# MegaAndLed.net
KiCad netlist of a schematic drawn in EAGLE
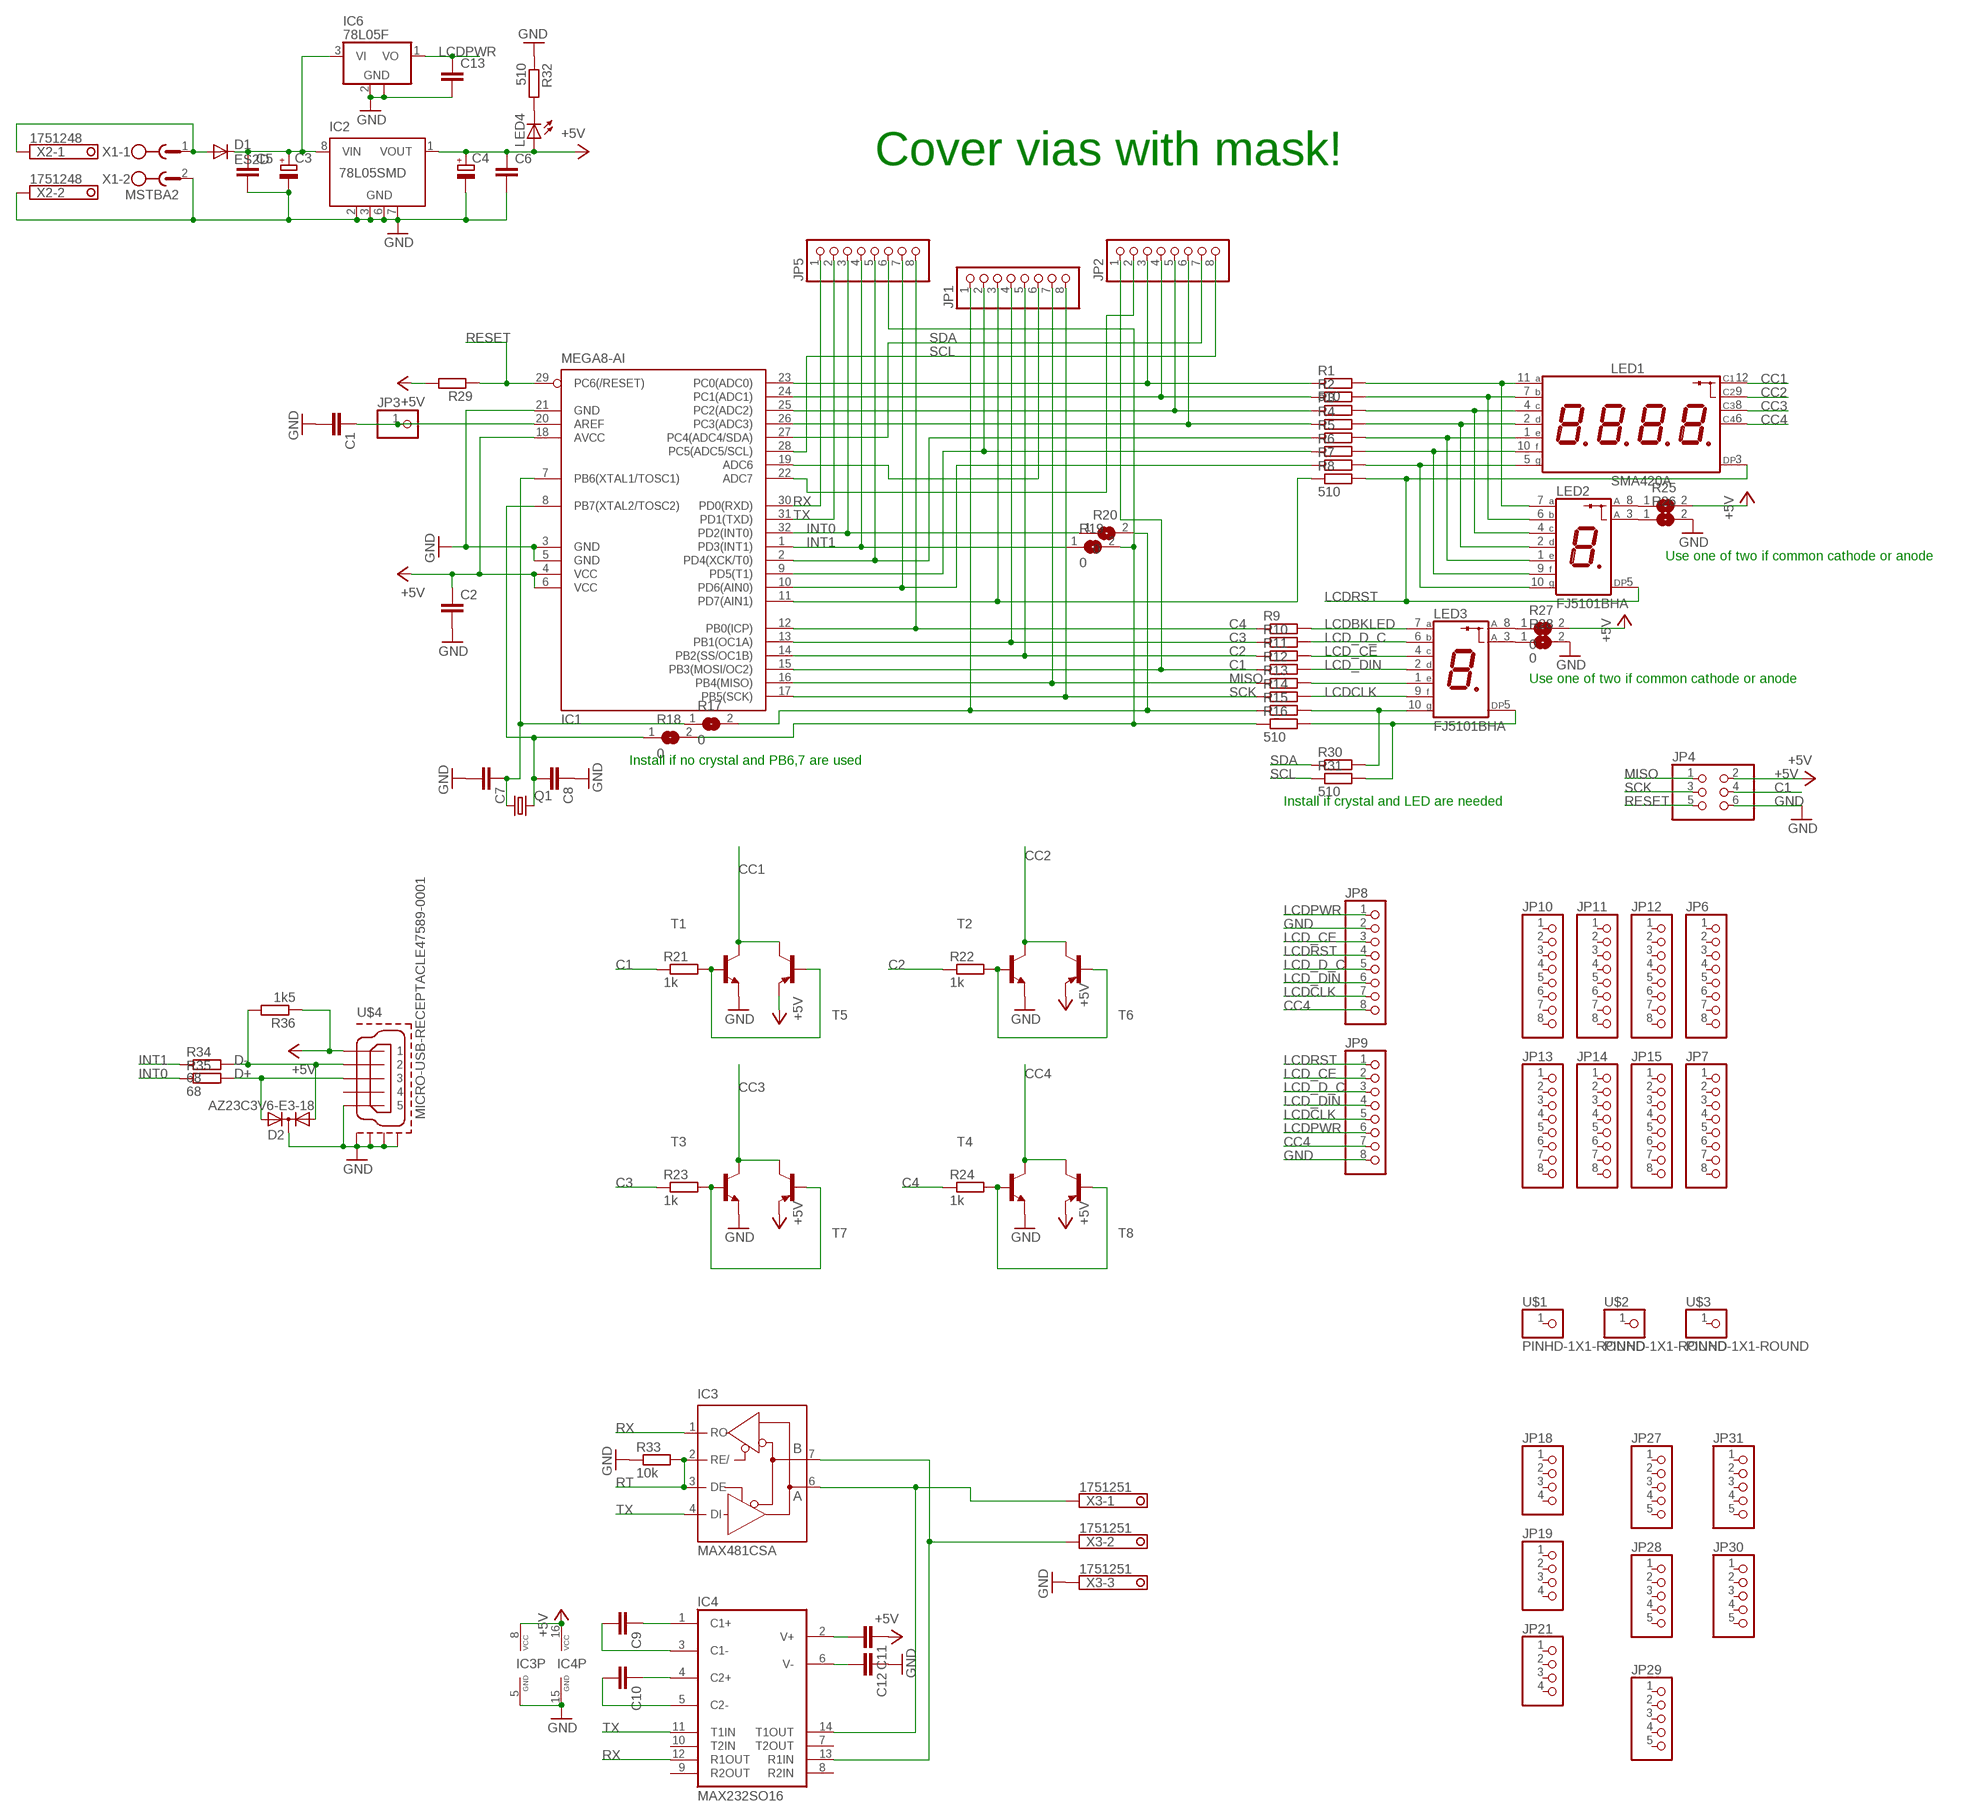
[diagram p0: schematic, sheet 1]

(export (version "E")
  (design (tool "Eeschema 10.0.6"))
  (components
    (comp (ref "C1")
      (value "C-EUC0805")
      (footprint "eagle-import:C0805")
      (libsource (lib "eagle-import") (part "C-EUC0805"))
    )
    (comp (ref "C2")
      (value "C-EUC0805")
      (footprint "eagle-import:C0805")
      (libsource (lib "eagle-import") (part "C-EUC0805"))
    )
    (comp (ref "C3")
      (value "CPOL-EUSMCC")
      (footprint "eagle-import:SMC_C")
      (libsource (lib "eagle-import") (part "CPOL-EUSMCC"))
    )
    (comp (ref "C4")
      (value "CPOL-EUSMCC")
      (footprint "eagle-import:SMC_C")
      (libsource (lib "eagle-import") (part "CPOL-EUSMCC"))
    )
    (comp (ref "C5")
      (value "C-EUC0805")
      (footprint "eagle-import:C0805")
      (libsource (lib "eagle-import") (part "C-EUC0805"))
    )
    (comp (ref "C6")
      (value "C-EUC0805")
      (footprint "eagle-import:C0805")
      (libsource (lib "eagle-import") (part "C-EUC0805"))
    )
    (comp (ref "C7")
      (value "C-EUC0805")
      (footprint "eagle-import:C0805")
      (libsource (lib "eagle-import") (part "C-EUC0805"))
    )
    (comp (ref "C8")
      (value "C-EUC0805")
      (footprint "eagle-import:C0805")
      (libsource (lib "eagle-import") (part "C-EUC0805"))
    )
    (comp (ref "C9")
      (value "C-EUC0805")
      (footprint "eagle-import:C0805")
      (libsource (lib "eagle-import") (part "C-EUC0805"))
    )
    (comp (ref "C10")
      (value "C-EUC0805")
      (footprint "eagle-import:C0805")
      (libsource (lib "eagle-import") (part "C-EUC0805"))
    )
    (comp (ref "C11")
      (value "C-EUC0805")
      (footprint "eagle-import:C0805")
      (libsource (lib "eagle-import") (part "C-EUC0805"))
    )
    (comp (ref "C12")
      (value "C-EUC0805")
      (footprint "eagle-import:C0805")
      (libsource (lib "eagle-import") (part "C-EUC0805"))
    )
    (comp (ref "C13")
      (value "C-EUC0805")
      (footprint "eagle-import:C0805")
      (libsource (lib "eagle-import") (part "C-EUC0805"))
    )
    (comp (ref "D1")
      (value "ES2D")
      (footprint "eagle-import:SMB")
      (libsource (lib "eagle-import") (part "ES2D"))
    )
    (comp (ref "D2")
      (value "AZ23C3V6-E3-18")
      (footprint "eagle-import:SOT23")
      (libsource (lib "eagle-import") (part "DIODE-2AC|CASOT23"))
    )
    (comp (ref "IC1")
      (value "MEGA8-AI")
      (footprint "eagle-import:TQFP32-08")
      (libsource (lib "eagle-import") (part "MEGA8-AI"))
    )
    (comp (ref "IC2")
      (value "78L05SMD")
      (footprint "eagle-import:SO08")
      (libsource (lib "eagle-import") (part "78LSMD05"))
    )
    (comp (ref "IC3")
      (value "MAX481CSA")
      (footprint "eagle-import:SO08")
      (libsource (lib "eagle-import") (part "MAX481CSA"))
    )
    (comp (ref "IC4")
      (value "MAX232SO16")
      (footprint "eagle-import:SO16")
      (libsource (lib "eagle-import") (part "MAX232SO16"))
    )
    (comp (ref "IC6")
      (value "78L05F")
      (footprint "eagle-import:SOT89")
      (libsource (lib "eagle-import") (part "78LF05"))
    )
    (comp (ref "JP1")
      (value "PINHD-1X8-ROUND")
      (footprint "eagle-import:1X08-ROUND")
      (libsource (lib "eagle-import") (part "PINHD-1X8-ROUND"))
    )
    (comp (ref "JP2")
      (value "PINHD-1X8-ROUND")
      (footprint "eagle-import:1X08-ROUND")
      (libsource (lib "eagle-import") (part "PINHD-1X8-ROUND"))
    )
    (comp (ref "JP3")
      (value "PINHD-1X1")
      (footprint "eagle-import:1X01")
      (libsource (lib "eagle-import") (part "PINHD-1X1"))
    )
    (comp (ref "JP4")
      (value "PINHD-2X3")
      (footprint "eagle-import:2X03")
      (libsource (lib "eagle-import") (part "PINHD-2X3"))
    )
    (comp (ref "JP5")
      (value "PINHD-1X8-ROUND")
      (footprint "eagle-import:1X08-ROUND")
      (libsource (lib "eagle-import") (part "PINHD-1X8-ROUND"))
    )
    (comp (ref "JP6")
      (value "PINHD-1X8-ROUND")
      (footprint "eagle-import:1X08-ROUND")
      (libsource (lib "eagle-import") (part "PINHD-1X8-ROUND"))
    )
    (comp (ref "JP7")
      (value "PINHD-1X8-ROUND")
      (footprint "eagle-import:1X08-ROUND")
      (libsource (lib "eagle-import") (part "PINHD-1X8-ROUND"))
    )
    (comp (ref "JP8")
      (value "PINHD-1X8-ROUND")
      (footprint "eagle-import:1X08-ROUND")
      (libsource (lib "eagle-import") (part "PINHD-1X8-ROUND"))
    )
    (comp (ref "JP9")
      (value "PINHD-1X8-ROUND")
      (footprint "eagle-import:1X08-ROUND")
      (libsource (lib "eagle-import") (part "PINHD-1X8-ROUND"))
    )
    (comp (ref "JP10")
      (value "PINHD-1X8-ROUND")
      (footprint "eagle-import:1X08-ROUND")
      (libsource (lib "eagle-import") (part "PINHD-1X8-ROUND"))
    )
    (comp (ref "JP11")
      (value "PINHD-1X8-ROUND")
      (footprint "eagle-import:1X08-ROUND")
      (libsource (lib "eagle-import") (part "PINHD-1X8-ROUND"))
    )
    (comp (ref "JP12")
      (value "PINHD-1X8-ROUND")
      (footprint "eagle-import:1X08-ROUND")
      (libsource (lib "eagle-import") (part "PINHD-1X8-ROUND"))
    )
    (comp (ref "JP13")
      (value "PINHD-1X8-ROUND")
      (footprint "eagle-import:1X08-ROUND")
      (libsource (lib "eagle-import") (part "PINHD-1X8-ROUND"))
    )
    (comp (ref "JP14")
      (value "PINHD-1X8-ROUND")
      (footprint "eagle-import:1X08-ROUND")
      (libsource (lib "eagle-import") (part "PINHD-1X8-ROUND"))
    )
    (comp (ref "JP15")
      (value "PINHD-1X8-ROUND")
      (footprint "eagle-import:1X08-ROUND")
      (libsource (lib "eagle-import") (part "PINHD-1X8-ROUND"))
    )
    (comp (ref "JP18")
      (value "PINHD-1X4-ROUND")
      (footprint "eagle-import:1X04-ROUND")
      (libsource (lib "eagle-import") (part "PINHD-1X4-ROUND"))
    )
    (comp (ref "JP19")
      (value "PINHD-1X4-ROUND")
      (footprint "eagle-import:1X04-ROUND")
      (libsource (lib "eagle-import") (part "PINHD-1X4-ROUND"))
    )
    (comp (ref "JP21")
      (value "PINHD-1X4-ROUND")
      (footprint "eagle-import:1X04-ROUND")
      (libsource (lib "eagle-import") (part "PINHD-1X4-ROUND"))
    )
    (comp (ref "JP27")
      (value "PINHD-1X5-ROUND")
      (footprint "eagle-import:1X05-ROUND")
      (libsource (lib "eagle-import") (part "PINHD-1X5-ROUND"))
    )
    (comp (ref "JP28")
      (value "PINHD-1X5-ROUND")
      (footprint "eagle-import:1X05-ROUND")
      (libsource (lib "eagle-import") (part "PINHD-1X5-ROUND"))
    )
    (comp (ref "JP29")
      (value "PINHD-1X5-ROUND")
      (footprint "eagle-import:1X05-ROUND")
      (libsource (lib "eagle-import") (part "PINHD-1X5-ROUND"))
    )
    (comp (ref "JP30")
      (value "PINHD-1X5-ROUND")
      (footprint "eagle-import:1X05-ROUND")
      (libsource (lib "eagle-import") (part "PINHD-1X5-ROUND"))
    )
    (comp (ref "JP31")
      (value "PINHD-1X5-ROUND")
      (footprint "eagle-import:1X05-ROUND")
      (libsource (lib "eagle-import") (part "PINHD-1X5-ROUND"))
    )
    (comp (ref "LED1")
      (value "SMA420A")
      (footprint "eagle-import:7X4-LED")
      (libsource (lib "eagle-import") (part "SMA420A"))
    )
    (comp (ref "LED2")
      (value "FJ5101BHA")
      (footprint "eagle-import:LA-401")
      (libsource (lib "eagle-import") (part "FJ5101BHA"))
    )
    (comp (ref "LED3")
      (value "FJ5101BHA")
      (footprint "eagle-import:LA-401")
      (libsource (lib "eagle-import") (part "FJ5101BHA"))
    )
    (comp (ref "LED4")
      (value "LEDCHIPLED_1206")
      (footprint "eagle-import:CHIPLED_1206")
      (libsource (lib "eagle-import") (part "LEDCHIPLED_1206"))
    )
    (comp (ref "Q1")
      (value "CRYSTALHC49U-H")
      (footprint "eagle-import:HC49U-H")
      (libsource (lib "eagle-import") (part "CRYSTALHC49U-H"))
    )
    (comp (ref "R1")
      (value "510")
      (footprint "eagle-import:R0805")
      (libsource (lib "eagle-import") (part "R-EU_R0805"))
    )
    (comp (ref "R2")
      (value "R-EU_R0805")
      (footprint "eagle-import:R0805")
      (libsource (lib "eagle-import") (part "R-EU_R0805"))
    )
    (comp (ref "R3")
      (value "R-EU_R0805")
      (footprint "eagle-import:R0805")
      (libsource (lib "eagle-import") (part "R-EU_R0805"))
    )
    (comp (ref "R4")
      (value "R-EU_R0805")
      (footprint "eagle-import:R0805")
      (libsource (lib "eagle-import") (part "R-EU_R0805"))
    )
    (comp (ref "R5")
      (value "R-EU_R0805")
      (footprint "eagle-import:R0805")
      (libsource (lib "eagle-import") (part "R-EU_R0805"))
    )
    (comp (ref "R6")
      (value "R-EU_R0805")
      (footprint "eagle-import:R0805")
      (libsource (lib "eagle-import") (part "R-EU_R0805"))
    )
    (comp (ref "R7")
      (value "R-EU_R0805")
      (footprint "eagle-import:R0805")
      (libsource (lib "eagle-import") (part "R-EU_R0805"))
    )
    (comp (ref "R8")
      (value "510")
      (footprint "eagle-import:R0805")
      (libsource (lib "eagle-import") (part "R-EU_R0805"))
    )
    (comp (ref "R9")
      (value "R-EU_R0805")
      (footprint "eagle-import:R0805")
      (libsource (lib "eagle-import") (part "R-EU_R0805"))
    )
    (comp (ref "R10")
      (value "R-EU_R0805")
      (footprint "eagle-import:R0805")
      (libsource (lib "eagle-import") (part "R-EU_R0805"))
    )
    (comp (ref "R11")
      (value "R-EU_R0805")
      (footprint "eagle-import:R0805")
      (libsource (lib "eagle-import") (part "R-EU_R0805"))
    )
    (comp (ref "R12")
      (value "R-EU_R0805")
      (footprint "eagle-import:R0805")
      (libsource (lib "eagle-import") (part "R-EU_R0805"))
    )
    (comp (ref "R13")
      (value "R-EU_R0805")
      (footprint "eagle-import:R0805")
      (libsource (lib "eagle-import") (part "R-EU_R0805"))
    )
    (comp (ref "R14")
      (value "R-EU_R0805")
      (footprint "eagle-import:R0805")
      (libsource (lib "eagle-import") (part "R-EU_R0805"))
    )
    (comp (ref "R15")
      (value "R-EU_R0805")
      (footprint "eagle-import:R0805")
      (libsource (lib "eagle-import") (part "R-EU_R0805"))
    )
    (comp (ref "R16")
      (value "510")
      (footprint "eagle-import:R0805")
      (libsource (lib "eagle-import") (part "R-EU_R0805"))
    )
    (comp (ref "R17") (value "0") (footprint "eagle-import:SJ") (libsource (lib "eagle-import") (part "SJ")))
    (comp (ref "R18") (value "0") (footprint "eagle-import:SJ") (libsource (lib "eagle-import") (part "SJ")))
    (comp (ref "R19") (value "0") (footprint "eagle-import:SJ") (libsource (lib "eagle-import") (part "SJ")))
    (comp (ref "R20") (value "0") (footprint "eagle-import:SJ") (libsource (lib "eagle-import") (part "SJ")))
    (comp (ref "R21")
      (value "1k")
      (footprint "eagle-import:R0805")
      (libsource (lib "eagle-import") (part "R-EU_R0805"))
    )
    (comp (ref "R22")
      (value "1k")
      (footprint "eagle-import:R0805")
      (libsource (lib "eagle-import") (part "R-EU_R0805"))
    )
    (comp (ref "R23")
      (value "1k")
      (footprint "eagle-import:R0805")
      (libsource (lib "eagle-import") (part "R-EU_R0805"))
    )
    (comp (ref "R24")
      (value "1k")
      (footprint "eagle-import:R0805")
      (libsource (lib "eagle-import") (part "R-EU_R0805"))
    )
    (comp (ref "R25") (value "SJ") (footprint "eagle-import:SJ") (libsource (lib "eagle-import") (part "SJ")))
    (comp (ref "R26") (value "SJ") (footprint "eagle-import:SJ") (libsource (lib "eagle-import") (part "SJ")))
    (comp (ref "R27") (value "0") (footprint "eagle-import:SJ") (libsource (lib "eagle-import") (part "SJ")))
    (comp (ref "R28") (value "0") (footprint "eagle-import:SJ") (libsource (lib "eagle-import") (part "SJ")))
    (comp (ref "R29")
      (value "R-EU_R0805")
      (footprint "eagle-import:R0805")
      (libsource (lib "eagle-import") (part "R-EU_R0805"))
    )
    (comp (ref "R30")
      (value "R-EU_R0805")
      (footprint "eagle-import:R0805")
      (libsource (lib "eagle-import") (part "R-EU_R0805"))
    )
    (comp (ref "R31")
      (value "510")
      (footprint "eagle-import:R0805")
      (libsource (lib "eagle-import") (part "R-EU_R0805"))
    )
    (comp (ref "R32")
      (value "510")
      (footprint "eagle-import:R0805")
      (libsource (lib "eagle-import") (part "R-EU_R0805"))
    )
    (comp (ref "R33")
      (value "10k")
      (footprint "eagle-import:R0805")
      (libsource (lib "eagle-import") (part "R-EU_R0805"))
    )
    (comp (ref "R34")
      (value "68")
      (footprint "eagle-import:R0805")
      (libsource (lib "eagle-import") (part "R-EU_R0805"))
    )
    (comp (ref "R35")
      (value "68")
      (footprint "eagle-import:R0805")
      (libsource (lib "eagle-import") (part "R-EU_R0805"))
    )
    (comp (ref "R36")
      (value "1k5")
      (footprint "eagle-import:R0805")
      (libsource (lib "eagle-import") (part "R-EU_R0805"))
    )
    (comp (ref "T1")
      (value "BCW31-NPN-SOT23-BEC")
      (footprint "eagle-import:SOT23-BEC")
      (libsource (lib "eagle-import") (part "-NPN-SOT23-BECBCW31"))
    )
    (comp (ref "T2")
      (value "BCW31-NPN-SOT23-BEC")
      (footprint "eagle-import:SOT23-BEC")
      (libsource (lib "eagle-import") (part "-NPN-SOT23-BECBCW31"))
    )
    (comp (ref "T3")
      (value "BCW31-NPN-SOT23-BEC")
      (footprint "eagle-import:SOT23-BEC")
      (libsource (lib "eagle-import") (part "-NPN-SOT23-BECBCW31"))
    )
    (comp (ref "T4")
      (value "BCW31-NPN-SOT23-BEC")
      (footprint "eagle-import:SOT23-BEC")
      (libsource (lib "eagle-import") (part "-NPN-SOT23-BECBCW31"))
    )
    (comp (ref "T5")
      (value "MMBTA56-SOT23")
      (footprint "eagle-import:SOT23")
      (libsource (lib "eagle-import") (part "-?SOT23MMBTA56"))
    )
    (comp (ref "T6")
      (value "MMBTA56-SOT23")
      (footprint "eagle-import:SOT23")
      (libsource (lib "eagle-import") (part "-?SOT23MMBTA56"))
    )
    (comp (ref "T7")
      (value "MMBTA56-SOT23")
      (footprint "eagle-import:SOT23")
      (libsource (lib "eagle-import") (part "-?SOT23MMBTA56"))
    )
    (comp (ref "T8")
      (value "MMBTA56-SOT23")
      (footprint "eagle-import:SOT23")
      (libsource (lib "eagle-import") (part "-?SOT23MMBTA56"))
    )
    (comp (ref "U$1")
      (value "PINHD-1X1-ROUND")
      (footprint "eagle-import:1X01-ROUND")
      (libsource (lib "eagle-import") (part "PINHD-1X1-ROUND"))
    )
    (comp (ref "U$2")
      (value "PINHD-1X1-ROUND")
      (footprint "eagle-import:1X01-ROUND")
      (libsource (lib "eagle-import") (part "PINHD-1X1-ROUND"))
    )
    (comp (ref "U$3")
      (value "PINHD-1X1-ROUND")
      (footprint "eagle-import:1X01-ROUND")
      (libsource (lib "eagle-import") (part "PINHD-1X1-ROUND"))
    )
    (comp (ref "U$4")
      (value "MICRO-USB-RECEPTACLE47589-0001")
      (footprint "eagle-import:47589-0001")
      (libsource (lib "eagle-import") (part "MICRO-USB-RECEPTACLE47589-0001"))
    )
    (comp (ref "X1")
      (value "MSTBA2")
      (footprint "eagle-import:MSTBA2")
      (libsource (lib "eagle-import") (part "MSTBA2"))
    )
    (comp (ref "X2")
      (value "1751248")
      (footprint "eagle-import:1751248")
      (libsource (lib "eagle-import") (part "1751248"))
    )
    (comp (ref "X3")
      (value "1751251")
      (footprint "eagle-import:1751251")
      (libsource (lib "eagle-import") (part "1751251"))
    )
  )
  (nets
    (net (code "1") (name "+5V") (class "Default")
      (node (ref "C11") (pin "1") (pinfunction "1_1") (pintype "passive"))
      (node (ref "C2") (pin "1") (pinfunction "1_1") (pintype "passive"))
      (node (ref "C4") (pin "+") (pinfunction "+_+") (pintype "passive"))
      (node (ref "C6") (pin "1") (pinfunction "1_1") (pintype "passive"))
      (node (ref "IC1") (pin "18") (pinfunction "AVCC_18") (pintype "power_in"))
      (node (ref "IC1") (pin "4") (pinfunction "VCC_4") (pintype "power_in"))
      (node (ref "IC1") (pin "6") (pinfunction "VCC_6") (pintype "power_in"))
      (node (ref "IC2") (pin "1") (pinfunction "VOUT_1") (pintype "output"))
      (node (ref "IC3") (pin "8") (pinfunction "VCC_8") (pintype "power_in"))
      (node (ref "IC4") (pin "16") (pinfunction "VCC_16") (pintype "power_in"))
      (node (ref "JP4") (pin "2") (pinfunction "2_2") (pintype "passive"))
      (node (ref "LED4") (pin "A") (pinfunction "A_A") (pintype "passive"))
      (node (ref "R25") (pin "2") (pinfunction "2_2") (pintype "passive"))
      (node (ref "R27") (pin "2") (pinfunction "2_2") (pintype "passive"))
      (node (ref "R29") (pin "2") (pinfunction "2_2") (pintype "passive"))
      (node (ref "R36") (pin "1") (pinfunction "1_1") (pintype "passive"))
      (node (ref "T5") (pin "2") (pinfunction "E_2") (pintype "passive"))
      (node (ref "T6") (pin "2") (pinfunction "E_2") (pintype "passive"))
      (node (ref "T7") (pin "2") (pinfunction "E_2") (pintype "passive"))
      (node (ref "T8") (pin "2") (pinfunction "E_2") (pintype "passive"))
      (node (ref "U$4") (pin "1") (pinfunction "1_1") (pintype "input"))
    )
    (net (code "2") (name "/C1") (class "Default")
      (node (ref "IC1") (pin "15") (pinfunction "PB3(MOSI/OC2)_15") (pintype "bidirectional"))
      (node (ref "JP2") (pin "1") (pinfunction "1_1") (pintype "passive"))
      (node (ref "JP4") (pin "4") (pinfunction "4_4") (pintype "passive"))
      (node (ref "R12") (pin "1") (pinfunction "1_1") (pintype "passive"))
      (node (ref "R21") (pin "1") (pinfunction "1_1") (pintype "passive"))
    )
    (net (code "3") (name "/C2") (class "Default")
      (node (ref "IC1") (pin "14") (pinfunction "PB2(SS/OC1B)_14") (pintype "bidirectional"))
      (node (ref "JP1") (pin "5") (pinfunction "5_5") (pintype "passive"))
      (node (ref "R11") (pin "1") (pinfunction "1_1") (pintype "passive"))
      (node (ref "R22") (pin "1") (pinfunction "1_1") (pintype "passive"))
    )
    (net (code "4") (name "/C3") (class "Default")
      (node (ref "IC1") (pin "13") (pinfunction "PB1(OC1A)_13") (pintype "bidirectional"))
      (node (ref "JP1") (pin "4") (pinfunction "4_4") (pintype "passive"))
      (node (ref "R10") (pin "1") (pinfunction "1_1") (pintype "passive"))
      (node (ref "R23") (pin "1") (pinfunction "1_1") (pintype "passive"))
    )
    (net (code "5") (name "/C4") (class "Default")
      (node (ref "IC1") (pin "12") (pinfunction "PB0(ICP)_12") (pintype "bidirectional"))
      (node (ref "JP5") (pin "8") (pinfunction "8_8") (pintype "passive"))
      (node (ref "R24") (pin "1") (pinfunction "1_1") (pintype "passive"))
      (node (ref "R9") (pin "1") (pinfunction "1_1") (pintype "passive"))
    )
    (net (code "6") (name "/CC1") (class "Default")
      (node (ref "LED1") (pin "12") (pinfunction "C_12") (pintype "passive"))
      (node (ref "T1") (pin "C") (pinfunction "C_C") (pintype "passive"))
      (node (ref "T5") (pin "3") (pinfunction "C_3") (pintype "passive"))
    )
    (net (code "7") (name "/CC2") (class "Default")
      (node (ref "LED1") (pin "9") (pinfunction "C_9") (pintype "passive"))
      (node (ref "T2") (pin "C") (pinfunction "C_C") (pintype "passive"))
      (node (ref "T6") (pin "3") (pinfunction "C_3") (pintype "passive"))
    )
    (net (code "8") (name "/CC3") (class "Default")
      (node (ref "LED1") (pin "8") (pinfunction "C_8") (pintype "passive"))
      (node (ref "T3") (pin "C") (pinfunction "C_C") (pintype "passive"))
      (node (ref "T7") (pin "3") (pinfunction "C_3") (pintype "passive"))
    )
    (net (code "9") (name "/CC4") (class "Default")
      (node (ref "JP8") (pin "8") (pinfunction "8_8") (pintype "passive"))
      (node (ref "JP9") (pin "7") (pinfunction "7_7") (pintype "passive"))
      (node (ref "LED1") (pin "6") (pinfunction "C_6") (pintype "passive"))
      (node (ref "T4") (pin "C") (pinfunction "C_C") (pintype "passive"))
      (node (ref "T8") (pin "3") (pinfunction "C_3") (pintype "passive"))
    )
    (net (code "10") (name "/D+") (class "Default")
      (node (ref "D2") (pin "2") (pinfunction "A2_2") (pintype "passive"))
      (node (ref "R35") (pin "2") (pinfunction "2_2") (pintype "passive"))
      (node (ref "U$4") (pin "3") (pinfunction "3_3") (pintype "input"))
    )
    (net (code "11") (name "/D-") (class "Default")
      (node (ref "D2") (pin "1") (pinfunction "A1_1") (pintype "passive"))
      (node (ref "R34") (pin "2") (pinfunction "2_2") (pintype "passive"))
      (node (ref "R36") (pin "2") (pinfunction "2_2") (pintype "passive"))
      (node (ref "U$4") (pin "2") (pinfunction "2_2") (pintype "input"))
    )
    (net (code "12") (name "/INT0") (class "Default")
      (node (ref "IC1") (pin "32") (pinfunction "PD2(INT0)_32") (pintype "bidirectional"))
      (node (ref "JP5") (pin "3") (pinfunction "3_3") (pintype "passive"))
      (node (ref "R20") (pin "1") (pinfunction "1_1") (pintype "passive"))
      (node (ref "R35") (pin "1") (pinfunction "1_1") (pintype "passive"))
    )
    (net (code "13") (name "/INT1") (class "Default")
      (node (ref "IC1") (pin "1") (pinfunction "PD3(INT1)_1") (pintype "bidirectional"))
      (node (ref "JP5") (pin "4") (pinfunction "4_4") (pintype "passive"))
      (node (ref "R19") (pin "1") (pinfunction "1_1") (pintype "passive"))
      (node (ref "R34") (pin "1") (pinfunction "1_1") (pintype "passive"))
    )
    (net (code "14") (name "/LCDBKLED") (class "Default")
      (node (ref "LED3") (pin "7") (pinfunction "A_7") (pintype "passive"))
      (node (ref "R9") (pin "2") (pinfunction "2_2") (pintype "passive"))
    )
    (net (code "15") (name "/LCDCLK") (class "Default")
      (node (ref "JP8") (pin "7") (pinfunction "7_7") (pintype "passive"))
      (node (ref "JP9") (pin "5") (pinfunction "5_5") (pintype "passive"))
      (node (ref "LED3") (pin "9") (pinfunction "F_9") (pintype "passive"))
      (node (ref "R14") (pin "2") (pinfunction "2_2") (pintype "passive"))
    )
    (net (code "16") (name "/LCDPWR") (class "Default")
      (node (ref "C13") (pin "1") (pinfunction "1_1") (pintype "passive"))
      (node (ref "IC6") (pin "1") (pinfunction "VO_1") (pintype "passive"))
      (node (ref "JP8") (pin "1") (pinfunction "1_1") (pintype "passive"))
      (node (ref "JP9") (pin "6") (pinfunction "6_6") (pintype "passive"))
    )
    (net (code "17") (name "/LCDRST") (class "Default")
      (node (ref "JP8") (pin "4") (pinfunction "4_4") (pintype "passive"))
      (node (ref "JP9") (pin "1") (pinfunction "1_1") (pintype "passive"))
      (node (ref "LED1") (pin "3") (pinfunction "DP_3") (pintype "passive"))
      (node (ref "LED2") (pin "5") (pinfunction "DP_5") (pintype "passive"))
      (node (ref "R8") (pin "2") (pinfunction "2_2") (pintype "passive"))
    )
    (net (code "18") (name "/LCD_CE") (class "Default")
      (node (ref "JP8") (pin "3") (pinfunction "3_3") (pintype "passive"))
      (node (ref "JP9") (pin "2") (pinfunction "2_2") (pintype "passive"))
      (node (ref "LED3") (pin "4") (pinfunction "C_4") (pintype "passive"))
      (node (ref "R11") (pin "2") (pinfunction "2_2") (pintype "passive"))
    )
    (net (code "19") (name "/LCD_DIN") (class "Default")
      (node (ref "JP8") (pin "6") (pinfunction "6_6") (pintype "passive"))
      (node (ref "JP9") (pin "4") (pinfunction "4_4") (pintype "passive"))
      (node (ref "LED3") (pin "2") (pinfunction "D_2") (pintype "passive"))
      (node (ref "R12") (pin "2") (pinfunction "2_2") (pintype "passive"))
    )
    (net (code "20") (name "/LCD_D_C") (class "Default")
      (node (ref "JP8") (pin "5") (pinfunction "5_5") (pintype "passive"))
      (node (ref "JP9") (pin "3") (pinfunction "3_3") (pintype "passive"))
      (node (ref "LED3") (pin "6") (pinfunction "B_6") (pintype "passive"))
      (node (ref "R10") (pin "2") (pinfunction "2_2") (pintype "passive"))
    )
    (net (code "21") (name "/MISO") (class "Default")
      (node (ref "IC1") (pin "16") (pinfunction "PB4(MISO)_16") (pintype "bidirectional"))
      (node (ref "JP1") (pin "7") (pinfunction "7_7") (pintype "passive"))
      (node (ref "JP4") (pin "1") (pinfunction "1_1") (pintype "passive"))
      (node (ref "R13") (pin "1") (pinfunction "1_1") (pintype "passive"))
    )
    (net (code "22") (name "/RESET") (class "Default")
      (node (ref "IC1") (pin "29") (pinfunction "PC6(/RESET)_29") (pintype "bidirectional"))
      (node (ref "JP4") (pin "5") (pinfunction "5_5") (pintype "passive"))
      (node (ref "R29") (pin "1") (pinfunction "1_1") (pintype "passive"))
    )
    (net (code "23") (name "/RT") (class "Default")
      (node (ref "IC3") (pin "2") (pinfunction "RE/_2") (pintype "input"))
      (node (ref "IC3") (pin "3") (pinfunction "DE_3") (pintype "input"))
      (node (ref "R33") (pin "2") (pinfunction "2_2") (pintype "passive"))
    )
    (net (code "24") (name "/RX") (class "Default")
      (node (ref "IC1") (pin "30") (pinfunction "PD0(RXD)_30") (pintype "bidirectional"))
      (node (ref "IC3") (pin "1") (pinfunction "RO_1") (pintype "output"))
      (node (ref "IC4") (pin "12") (pinfunction "R1OUT_12") (pintype "output"))
      (node (ref "JP5") (pin "1") (pinfunction "1_1") (pintype "passive"))
    )
    (net (code "25") (name "/SCK") (class "Default")
      (node (ref "IC1") (pin "17") (pinfunction "PB5(SCK)_17") (pintype "bidirectional"))
      (node (ref "JP1") (pin "8") (pinfunction "8_8") (pintype "passive"))
      (node (ref "JP4") (pin "3") (pinfunction "3_3") (pintype "passive"))
      (node (ref "R14") (pin "1") (pinfunction "1_1") (pintype "passive"))
    )
    (net (code "26") (name "/SCL") (class "Default")
      (node (ref "IC1") (pin "28") (pinfunction "PC5(ADC5/SCL)_28") (pintype "bidirectional"))
      (node (ref "JP2") (pin "8") (pinfunction "8_8") (pintype "passive"))
      (node (ref "R31") (pin "1") (pinfunction "1_1") (pintype "passive"))
    )
    (net (code "27") (name "/SDA") (class "Default")
      (node (ref "IC1") (pin "27") (pinfunction "PC4(ADC4/SDA)_27") (pintype "bidirectional"))
      (node (ref "JP2") (pin "7") (pinfunction "7_7") (pintype "passive"))
      (node (ref "R30") (pin "1") (pinfunction "1_1") (pintype "passive"))
    )
    (net (code "28") (name "/TX") (class "Default")
      (node (ref "IC1") (pin "31") (pinfunction "PD1(TXD)_31") (pintype "bidirectional"))
      (node (ref "IC3") (pin "4") (pinfunction "DI_4") (pintype "input"))
      (node (ref "IC4") (pin "11") (pinfunction "T1IN_11") (pintype "input"))
      (node (ref "JP5") (pin "2") (pinfunction "2_2") (pintype "passive"))
    )
    (net (code "29") (name "GND") (class "Default")
      (node (ref "C1") (pin "2") (pinfunction "2_2") (pintype "passive"))
      (node (ref "C12") (pin "1") (pinfunction "1_1") (pintype "passive"))
      (node (ref "C13") (pin "2") (pinfunction "2_2") (pintype "passive"))
      (node (ref "C2") (pin "2") (pinfunction "2_2") (pintype "passive"))
      (node (ref "C3") (pin "-") (pinfunction "-_-") (pintype "passive"))
      (node (ref "C4") (pin "-") (pinfunction "-_-") (pintype "passive"))
      (node (ref "C5") (pin "2") (pinfunction "2_2") (pintype "passive"))
      (node (ref "C6") (pin "2") (pinfunction "2_2") (pintype "passive"))
      (node (ref "C7") (pin "2") (pinfunction "2_2") (pintype "passive"))
      (node (ref "C8") (pin "1") (pinfunction "1_1") (pintype "passive"))
      (node (ref "D2") (pin "3") (pinfunction "C_3") (pintype "passive"))
      (node (ref "IC1") (pin "21") (pinfunction "GND_21") (pintype "power_in"))
      (node (ref "IC1") (pin "3") (pinfunction "GND_3") (pintype "power_in"))
      (node (ref "IC1") (pin "5") (pinfunction "GND_5") (pintype "power_in"))
      (node (ref "IC2") (pin "2") (pinfunction "GND_2") (pintype "power_in"))
      (node (ref "IC2") (pin "3") (pinfunction "GND_3") (pintype "power_in"))
      (node (ref "IC2") (pin "6") (pinfunction "GND_6") (pintype "power_in"))
      (node (ref "IC2") (pin "7") (pinfunction "GND_7") (pintype "power_in"))
      (node (ref "IC3") (pin "5") (pinfunction "GND_5") (pintype "power_in"))
      (node (ref "IC4") (pin "15") (pinfunction "GND_15") (pintype "power_in"))
      (node (ref "IC6") (pin "2") (pinfunction "GND_2") (pintype "passive"))
      (node (ref "IC6") (pin "2@1") (pinfunction "GND_2@1") (pintype "passive"))
      (node (ref "JP4") (pin "6") (pinfunction "6_6") (pintype "passive"))
      (node (ref "JP8") (pin "2") (pinfunction "2_2") (pintype "passive"))
      (node (ref "JP9") (pin "8") (pinfunction "8_8") (pintype "passive"))
      (node (ref "R26") (pin "2") (pinfunction "2_2") (pintype "passive"))
      (node (ref "R28") (pin "2") (pinfunction "2_2") (pintype "passive"))
      (node (ref "R32") (pin "1") (pinfunction "1_1") (pintype "passive"))
      (node (ref "R33") (pin "1") (pinfunction "1_1") (pintype "passive"))
      (node (ref "T1") (pin "E") (pinfunction "E_E") (pintype "passive"))
      (node (ref "T2") (pin "E") (pinfunction "E_E") (pintype "passive"))
      (node (ref "T3") (pin "E") (pinfunction "E_E") (pintype "passive"))
      (node (ref "T4") (pin "E") (pinfunction "E_E") (pintype "passive"))
      (node (ref "U$4") (pin "5") (pinfunction "5_5") (pintype "input"))
      (node (ref "U$4") (pin "CASING1") (pinfunction "GND1_CASING1") (pintype "bidirectional"))
      (node (ref "U$4") (pin "CASING2") (pinfunction "GND2_CASING2") (pintype "bidirectional"))
      (node (ref "U$4") (pin "CASING3") (pinfunction "GND3_CASING3") (pintype "bidirectional"))
      (node (ref "U$4") (pin "CASING4") (pinfunction "GND4_CASING4") (pintype "bidirectional"))
      (node (ref "X1") (pin "2") (pinfunction "1_2") (pintype "passive"))
      (node (ref "X2") (pin "2") (pinfunction "K_2") (pintype "passive"))
      (node (ref "X3") (pin "3") (pinfunction "K_3") (pintype "passive"))
    )
    (net (code "30") (name "Net-(IC1-ADC6)") (class "Default")
      (node (ref "IC1") (pin "19") (pinfunction "ADC6_19") (pintype "bidirectional"))
      (node (ref "JP1") (pin "6") (pinfunction "6_6") (pintype "passive"))
    )
    (net (code "31") (name "Net-(IC1-ADC7)") (class "Default")
      (node (ref "IC1") (pin "22") (pinfunction "ADC7_22") (pintype "bidirectional"))
      (node (ref "JP2") (pin "2") (pinfunction "2_2") (pintype "passive"))
    )
    (net (code "32") (name "Net-(IC1-AREF)") (class "Default")
      (node (ref "C1") (pin "1") (pinfunction "1_1") (pintype "passive"))
      (node (ref "IC1") (pin "20") (pinfunction "AREF_20") (pintype "passive"))
      (node (ref "JP3") (pin "1") (pinfunction "1_1") (pintype "passive"))
    )
    (net (code "33") (name "Net-(IC1-PB6(XTAL1{slash}TOSC1))") (class "Default")
      (node (ref "C7") (pin "1") (pinfunction "1_1") (pintype "passive"))
      (node (ref "IC1") (pin "7") (pinfunction "PB6(XTAL1/TOSC1)_7") (pintype "bidirectional"))
      (node (ref "Q1") (pin "1") (pinfunction "1_1") (pintype "passive"))
      (node (ref "R17") (pin "1") (pinfunction "1_1") (pintype "passive"))
    )
    (net (code "34") (name "Net-(IC1-PB7(XTAL2{slash}TOSC2))") (class "Default")
      (node (ref "C8") (pin "2") (pinfunction "2_2") (pintype "passive"))
      (node (ref "IC1") (pin "8") (pinfunction "PB7(XTAL2/TOSC2)_8") (pintype "bidirectional"))
      (node (ref "Q1") (pin "2") (pinfunction "2_2") (pintype "passive"))
      (node (ref "R18") (pin "1") (pinfunction "1_1") (pintype "passive"))
    )
    (net (code "35") (name "Net-(IC1-PC0(ADC0))") (class "Default")
      (node (ref "IC1") (pin "23") (pinfunction "PC0(ADC0)_23") (pintype "bidirectional"))
      (node (ref "JP2") (pin "3") (pinfunction "3_3") (pintype "passive"))
      (node (ref "R1") (pin "1") (pinfunction "1_1") (pintype "passive"))
    )
    (net (code "36") (name "Net-(IC1-PC1(ADC1))") (class "Default")
      (node (ref "IC1") (pin "24") (pinfunction "PC1(ADC1)_24") (pintype "bidirectional"))
      (node (ref "JP2") (pin "4") (pinfunction "4_4") (pintype "passive"))
      (node (ref "R2") (pin "1") (pinfunction "1_1") (pintype "passive"))
    )
    (net (code "37") (name "Net-(IC1-PC2(ADC2))") (class "Default")
      (node (ref "IC1") (pin "25") (pinfunction "PC2(ADC2)_25") (pintype "bidirectional"))
      (node (ref "JP2") (pin "5") (pinfunction "5_5") (pintype "passive"))
      (node (ref "R3") (pin "1") (pinfunction "1_1") (pintype "passive"))
    )
    (net (code "38") (name "Net-(IC1-PC3(ADC3))") (class "Default")
      (node (ref "IC1") (pin "26") (pinfunction "PC3(ADC3)_26") (pintype "bidirectional"))
      (node (ref "JP2") (pin "6") (pinfunction "6_6") (pintype "passive"))
      (node (ref "R4") (pin "1") (pinfunction "1_1") (pintype "passive"))
    )
    (net (code "39") (name "Net-(IC1-PD4(XCK{slash}T0))") (class "Default")
      (node (ref "IC1") (pin "2") (pinfunction "PD4(XCK/T0)_2") (pintype "bidirectional"))
      (node (ref "JP5") (pin "5") (pinfunction "5_5") (pintype "passive"))
      (node (ref "R5") (pin "1") (pinfunction "1_1") (pintype "passive"))
    )
    (net (code "40") (name "Net-(IC1-PD5(T1))") (class "Default")
      (node (ref "IC1") (pin "9") (pinfunction "PD5(T1)_9") (pintype "bidirectional"))
      (node (ref "JP1") (pin "2") (pinfunction "2_2") (pintype "passive"))
      (node (ref "R6") (pin "1") (pinfunction "1_1") (pintype "passive"))
    )
    (net (code "41") (name "Net-(IC1-PD6(AIN0))") (class "Default")
      (node (ref "IC1") (pin "10") (pinfunction "PD6(AIN0)_10") (pintype "bidirectional"))
      (node (ref "JP5") (pin "7") (pinfunction "7_7") (pintype "passive"))
      (node (ref "R7") (pin "1") (pinfunction "1_1") (pintype "passive"))
    )
    (net (code "42") (name "Net-(IC1-PD7(AIN1))") (class "Default")
      (node (ref "IC1") (pin "11") (pinfunction "PD7(AIN1)_11") (pintype "bidirectional"))
      (node (ref "JP1") (pin "3") (pinfunction "3_3") (pintype "passive"))
      (node (ref "R8") (pin "1") (pinfunction "1_1") (pintype "passive"))
    )
    (net (code "43") (name "Net-(IC2A-VIN)") (class "Default")
      (node (ref "C3") (pin "+") (pinfunction "+_+") (pintype "passive"))
      (node (ref "C5") (pin "1") (pinfunction "1_1") (pintype "passive"))
      (node (ref "D1") (pin "C") (pinfunction "C_C") (pintype "passive"))
      (node (ref "IC2") (pin "8") (pinfunction "VIN_8") (pintype "passive"))
      (node (ref "IC6") (pin "3") (pinfunction "VI_3") (pintype "input"))
    )
    (net (code "44") (name "Net-(IC3A-A)") (class "Default")
      (node (ref "IC3") (pin "6") (pinfunction "A_6") (pintype "passive"))
      (node (ref "IC4") (pin "14") (pinfunction "T1OUT_14") (pintype "output"))
      (node (ref "X3") (pin "1") (pinfunction "K_1") (pintype "passive"))
    )
    (net (code "45") (name "Net-(IC3A-B)") (class "Default")
      (node (ref "IC3") (pin "7") (pinfunction "B_7") (pintype "passive"))
      (node (ref "IC4") (pin "13") (pinfunction "R1IN_13") (pintype "input"))
      (node (ref "X3") (pin "2") (pinfunction "K_2") (pintype "passive"))
    )
    (net (code "46") (name "Net-(IC4A-C1+)") (class "Default")
      (node (ref "C9") (pin "1") (pinfunction "1_1") (pintype "passive"))
      (node (ref "IC4") (pin "1") (pinfunction "C1+_1") (pintype "bidirectional"))
    )
    (net (code "47") (name "Net-(IC4A-C1-)") (class "Default")
      (node (ref "C9") (pin "2") (pinfunction "2_2") (pintype "passive"))
      (node (ref "IC4") (pin "3") (pinfunction "C1-_3") (pintype "bidirectional"))
    )
    (net (code "48") (name "Net-(IC4A-C2+)") (class "Default")
      (node (ref "C10") (pin "1") (pinfunction "1_1") (pintype "passive"))
      (node (ref "IC4") (pin "4") (pinfunction "C2+_4") (pintype "bidirectional"))
    )
    (net (code "49") (name "Net-(IC4A-C2-)") (class "Default")
      (node (ref "C10") (pin "2") (pinfunction "2_2") (pintype "passive"))
      (node (ref "IC4") (pin "5") (pinfunction "C2-_5") (pintype "bidirectional"))
    )
    (net (code "50") (name "Net-(IC4A-V+)") (class "Default")
      (node (ref "C11") (pin "2") (pinfunction "2_2") (pintype "passive"))
      (node (ref "IC4") (pin "2") (pinfunction "V+_2") (pintype "bidirectional"))
    )
    (net (code "51") (name "Net-(IC4A-V-)") (class "Default")
      (node (ref "C12") (pin "2") (pinfunction "2_2") (pintype "passive"))
      (node (ref "IC4") (pin "6") (pinfunction "V-_6") (pintype "bidirectional"))
    )
    (net (code "52") (name "Net-(JP1-Pad1)") (class "Default")
      (node (ref "JP1") (pin "1") (pinfunction "1_1") (pintype "passive"))
      (node (ref "R15") (pin "1") (pinfunction "1_1") (pintype "passive"))
      (node (ref "R17") (pin "2") (pinfunction "2_2") (pintype "passive"))
      (node (ref "R20") (pin "2") (pinfunction "2_2") (pintype "passive"))
    )
    (net (code "53") (name "Net-(JP5-Pad6)") (class "Default")
      (node (ref "JP5") (pin "6") (pinfunction "6_6") (pintype "passive"))
      (node (ref "R16") (pin "1") (pinfunction "1_1") (pintype "passive"))
      (node (ref "R18") (pin "2") (pinfunction "2_2") (pintype "passive"))
      (node (ref "R19") (pin "2") (pinfunction "2_2") (pintype "passive"))
    )
    (net (code "54") (name "Net-(LED1-A)") (class "Default")
      (node (ref "LED1") (pin "11") (pinfunction "A_11") (pintype "passive"))
      (node (ref "LED2") (pin "7") (pinfunction "A_7") (pintype "passive"))
      (node (ref "R1") (pin "2") (pinfunction "2_2") (pintype "passive"))
    )
    (net (code "55") (name "Net-(LED1-B)") (class "Default")
      (node (ref "LED1") (pin "7") (pinfunction "B_7") (pintype "passive"))
      (node (ref "LED2") (pin "6") (pinfunction "B_6") (pintype "passive"))
      (node (ref "R2") (pin "2") (pinfunction "2_2") (pintype "passive"))
    )
    (net (code "56") (name "Net-(LED1-C-Pad4)") (class "Default")
      (node (ref "LED1") (pin "4") (pinfunction "C_4") (pintype "passive"))
      (node (ref "LED2") (pin "4") (pinfunction "C_4") (pintype "passive"))
      (node (ref "R3") (pin "2") (pinfunction "2_2") (pintype "passive"))
    )
    (net (code "57") (name "Net-(LED1-D)") (class "Default")
      (node (ref "LED1") (pin "2") (pinfunction "D_2") (pintype "passive"))
      (node (ref "LED2") (pin "2") (pinfunction "D_2") (pintype "passive"))
      (node (ref "R4") (pin "2") (pinfunction "2_2") (pintype "passive"))
    )
    (net (code "58") (name "Net-(LED1-E)") (class "Default")
      (node (ref "LED1") (pin "1") (pinfunction "E_1") (pintype "passive"))
      (node (ref "LED2") (pin "1") (pinfunction "E_1") (pintype "passive"))
      (node (ref "R5") (pin "2") (pinfunction "2_2") (pintype "passive"))
    )
    (net (code "59") (name "Net-(LED1-F)") (class "Default")
      (node (ref "LED1") (pin "10") (pinfunction "F_10") (pintype "passive"))
      (node (ref "LED2") (pin "9") (pinfunction "F_9") (pintype "passive"))
      (node (ref "R6") (pin "2") (pinfunction "2_2") (pintype "passive"))
    )
    (net (code "60") (name "Net-(LED1-G)") (class "Default")
      (node (ref "LED1") (pin "5") (pinfunction "G_5") (pintype "passive"))
      (node (ref "LED2") (pin "10") (pinfunction "G_10") (pintype "passive"))
      (node (ref "R7") (pin "2") (pinfunction "2_2") (pintype "passive"))
    )
    (net (code "61") (name "Net-(LED2-C-Pad3)") (class "Default")
      (node (ref "LED2") (pin "3") (pinfunction "C_3") (pintype "passive"))
      (node (ref "R26") (pin "1") (pinfunction "1_1") (pintype "passive"))
    )
    (net (code "62") (name "Net-(LED2-C-Pad8)") (class "Default")
      (node (ref "LED2") (pin "8") (pinfunction "C_8") (pintype "passive"))
      (node (ref "R25") (pin "1") (pinfunction "1_1") (pintype "passive"))
    )
    (net (code "63") (name "Net-(LED3-C-Pad3)") (class "Default")
      (node (ref "LED3") (pin "3") (pinfunction "C_3") (pintype "passive"))
      (node (ref "R28") (pin "1") (pinfunction "1_1") (pintype "passive"))
    )
    (net (code "64") (name "Net-(LED3-C-Pad8)") (class "Default")
      (node (ref "LED3") (pin "8") (pinfunction "C_8") (pintype "passive"))
      (node (ref "R27") (pin "1") (pinfunction "1_1") (pintype "passive"))
    )
    (net (code "65") (name "Net-(LED3-DP)") (class "Default")
      (node (ref "LED3") (pin "5") (pinfunction "DP_5") (pintype "passive"))
      (node (ref "R16") (pin "2") (pinfunction "2_2") (pintype "passive"))
      (node (ref "R31") (pin "2") (pinfunction "2_2") (pintype "passive"))
    )
    (net (code "66") (name "Net-(LED3-E)") (class "Default")
      (node (ref "LED3") (pin "1") (pinfunction "E_1") (pintype "passive"))
      (node (ref "R13") (pin "2") (pinfunction "2_2") (pintype "passive"))
    )
    (net (code "67") (name "Net-(LED3-G)") (class "Default")
      (node (ref "LED3") (pin "10") (pinfunction "G_10") (pintype "passive"))
      (node (ref "R15") (pin "2") (pinfunction "2_2") (pintype "passive"))
      (node (ref "R30") (pin "2") (pinfunction "2_2") (pintype "passive"))
    )
    (net (code "68") (name "Net-(LED4-PadC)") (class "Default")
      (node (ref "LED4") (pin "C") (pinfunction "C_C") (pintype "passive"))
      (node (ref "R32") (pin "2") (pinfunction "2_2") (pintype "passive"))
    )
    (net (code "69") (name "Net-(T5-B)") (class "Default")
      (node (ref "R21") (pin "2") (pinfunction "2_2") (pintype "passive"))
      (node (ref "T1") (pin "B") (pinfunction "B_B") (pintype "passive"))
      (node (ref "T5") (pin "1") (pinfunction "B_1") (pintype "passive"))
    )
    (net (code "70") (name "Net-(T6-B)") (class "Default")
      (node (ref "R22") (pin "2") (pinfunction "2_2") (pintype "passive"))
      (node (ref "T2") (pin "B") (pinfunction "B_B") (pintype "passive"))
      (node (ref "T6") (pin "1") (pinfunction "B_1") (pintype "passive"))
    )
    (net (code "71") (name "Net-(T7-B)") (class "Default")
      (node (ref "R23") (pin "2") (pinfunction "2_2") (pintype "passive"))
      (node (ref "T3") (pin "B") (pinfunction "B_B") (pintype "passive"))
      (node (ref "T7") (pin "1") (pinfunction "B_1") (pintype "passive"))
    )
    (net (code "72") (name "Net-(T8-B)") (class "Default")
      (node (ref "R24") (pin "2") (pinfunction "2_2") (pintype "passive"))
      (node (ref "T4") (pin "B") (pinfunction "B_B") (pintype "passive"))
      (node (ref "T8") (pin "1") (pinfunction "B_1") (pintype "passive"))
    )
    (net (code "73") (name "Net-(X2A-K)") (class "Default")
      (node (ref "D1") (pin "A") (pinfunction "A_A") (pintype "passive"))
      (node (ref "X1") (pin "1") (pinfunction "1_1") (pintype "passive"))
      (node (ref "X2") (pin "1") (pinfunction "K_1") (pintype "passive"))
    )
    (net (code "74") (name "unconnected-(IC4A-R2IN-Pad8)") (class "Default")
      (node (ref "IC4") (pin "8") (pinfunction "R2IN_8") (pintype "input"))
    )
    (net (code "75") (name "unconnected-(IC4A-R2OUT-Pad9)") (class "Default")
      (node (ref "IC4") (pin "9") (pinfunction "R2OUT_9") (pintype "output"))
    )
    (net (code "76") (name "unconnected-(IC4A-T2IN-Pad10)") (class "Default")
      (node (ref "IC4") (pin "10") (pinfunction "T2IN_10") (pintype "input"))
    )
    (net (code "77") (name "unconnected-(IC4A-T2OUT-Pad7)") (class "Default")
      (node (ref "IC4") (pin "7") (pinfunction "T2OUT_7") (pintype "output"))
    )
    (net (code "78") (name "unconnected-(JP6-Pad1)") (class "Default")
      (node (ref "JP6") (pin "1") (pinfunction "1_1") (pintype "passive"))
    )
    (net (code "79") (name "unconnected-(JP6-Pad2)") (class "Default")
      (node (ref "JP6") (pin "2") (pinfunction "2_2") (pintype "passive"))
    )
    (net (code "80") (name "unconnected-(JP6-Pad3)") (class "Default")
      (node (ref "JP6") (pin "3") (pinfunction "3_3") (pintype "passive"))
    )
    (net (code "81") (name "unconnected-(JP6-Pad4)") (class "Default")
      (node (ref "JP6") (pin "4") (pinfunction "4_4") (pintype "passive"))
    )
    (net (code "82") (name "unconnected-(JP6-Pad5)") (class "Default")
      (node (ref "JP6") (pin "5") (pinfunction "5_5") (pintype "passive"))
    )
    (net (code "83") (name "unconnected-(JP6-Pad6)") (class "Default")
      (node (ref "JP6") (pin "6") (pinfunction "6_6") (pintype "passive"))
    )
    (net (code "84") (name "unconnected-(JP6-Pad7)") (class "Default")
      (node (ref "JP6") (pin "7") (pinfunction "7_7") (pintype "passive"))
    )
    (net (code "85") (name "unconnected-(JP6-Pad8)") (class "Default")
      (node (ref "JP6") (pin "8") (pinfunction "8_8") (pintype "passive"))
    )
    (net (code "86") (name "unconnected-(JP7-Pad1)") (class "Default")
      (node (ref "JP7") (pin "1") (pinfunction "1_1") (pintype "passive"))
    )
    (net (code "87") (name "unconnected-(JP7-Pad2)") (class "Default")
      (node (ref "JP7") (pin "2") (pinfunction "2_2") (pintype "passive"))
    )
    (net (code "88") (name "unconnected-(JP7-Pad3)") (class "Default")
      (node (ref "JP7") (pin "3") (pinfunction "3_3") (pintype "passive"))
    )
    (net (code "89") (name "unconnected-(JP7-Pad4)") (class "Default")
      (node (ref "JP7") (pin "4") (pinfunction "4_4") (pintype "passive"))
    )
    (net (code "90") (name "unconnected-(JP7-Pad5)") (class "Default")
      (node (ref "JP7") (pin "5") (pinfunction "5_5") (pintype "passive"))
    )
    (net (code "91") (name "unconnected-(JP7-Pad6)") (class "Default")
      (node (ref "JP7") (pin "6") (pinfunction "6_6") (pintype "passive"))
    )
    (net (code "92") (name "unconnected-(JP7-Pad7)") (class "Default")
      (node (ref "JP7") (pin "7") (pinfunction "7_7") (pintype "passive"))
    )
    (net (code "93") (name "unconnected-(JP7-Pad8)") (class "Default")
      (node (ref "JP7") (pin "8") (pinfunction "8_8") (pintype "passive"))
    )
    (net (code "94") (name "unconnected-(JP10-Pad1)") (class "Default")
      (node (ref "JP10") (pin "1") (pinfunction "1_1") (pintype "passive"))
    )
    (net (code "95") (name "unconnected-(JP10-Pad2)") (class "Default")
      (node (ref "JP10") (pin "2") (pinfunction "2_2") (pintype "passive"))
    )
    (net (code "96") (name "unconnected-(JP10-Pad3)") (class "Default")
      (node (ref "JP10") (pin "3") (pinfunction "3_3") (pintype "passive"))
    )
    (net (code "97") (name "unconnected-(JP10-Pad4)") (class "Default")
      (node (ref "JP10") (pin "4") (pinfunction "4_4") (pintype "passive"))
    )
    (net (code "98") (name "unconnected-(JP10-Pad5)") (class "Default")
      (node (ref "JP10") (pin "5") (pinfunction "5_5") (pintype "passive"))
    )
    (net (code "99") (name "unconnected-(JP10-Pad6)") (class "Default")
      (node (ref "JP10") (pin "6") (pinfunction "6_6") (pintype "passive"))
    )
    (net (code "100") (name "unconnected-(JP10-Pad7)") (class "Default")
      (node (ref "JP10") (pin "7") (pinfunction "7_7") (pintype "passive"))
    )
    (net (code "101") (name "unconnected-(JP10-Pad8)") (class "Default")
      (node (ref "JP10") (pin "8") (pinfunction "8_8") (pintype "passive"))
    )
    (net (code "102") (name "unconnected-(JP11-Pad1)") (class "Default")
      (node (ref "JP11") (pin "1") (pinfunction "1_1") (pintype "passive"))
    )
    (net (code "103") (name "unconnected-(JP11-Pad2)") (class "Default")
      (node (ref "JP11") (pin "2") (pinfunction "2_2") (pintype "passive"))
    )
    (net (code "104") (name "unconnected-(JP11-Pad3)") (class "Default")
      (node (ref "JP11") (pin "3") (pinfunction "3_3") (pintype "passive"))
    )
    (net (code "105") (name "unconnected-(JP11-Pad4)") (class "Default")
      (node (ref "JP11") (pin "4") (pinfunction "4_4") (pintype "passive"))
    )
    (net (code "106") (name "unconnected-(JP11-Pad5)") (class "Default")
      (node (ref "JP11") (pin "5") (pinfunction "5_5") (pintype "passive"))
    )
    (net (code "107") (name "unconnected-(JP11-Pad6)") (class "Default")
      (node (ref "JP11") (pin "6") (pinfunction "6_6") (pintype "passive"))
    )
    (net (code "108") (name "unconnected-(JP11-Pad7)") (class "Default")
      (node (ref "JP11") (pin "7") (pinfunction "7_7") (pintype "passive"))
    )
    (net (code "109") (name "unconnected-(JP11-Pad8)") (class "Default")
      (node (ref "JP11") (pin "8") (pinfunction "8_8") (pintype "passive"))
    )
    (net (code "110") (name "unconnected-(JP12-Pad1)") (class "Default")
      (node (ref "JP12") (pin "1") (pinfunction "1_1") (pintype "passive"))
    )
    (net (code "111") (name "unconnected-(JP12-Pad2)") (class "Default")
      (node (ref "JP12") (pin "2") (pinfunction "2_2") (pintype "passive"))
    )
    (net (code "112") (name "unconnected-(JP12-Pad3)") (class "Default")
      (node (ref "JP12") (pin "3") (pinfunction "3_3") (pintype "passive"))
    )
    (net (code "113") (name "unconnected-(JP12-Pad4)") (class "Default")
      (node (ref "JP12") (pin "4") (pinfunction "4_4") (pintype "passive"))
    )
    (net (code "114") (name "unconnected-(JP12-Pad5)") (class "Default")
      (node (ref "JP12") (pin "5") (pinfunction "5_5") (pintype "passive"))
    )
    (net (code "115") (name "unconnected-(JP12-Pad6)") (class "Default")
      (node (ref "JP12") (pin "6") (pinfunction "6_6") (pintype "passive"))
    )
    (net (code "116") (name "unconnected-(JP12-Pad7)") (class "Default")
      (node (ref "JP12") (pin "7") (pinfunction "7_7") (pintype "passive"))
    )
    (net (code "117") (name "unconnected-(JP12-Pad8)") (class "Default")
      (node (ref "JP12") (pin "8") (pinfunction "8_8") (pintype "passive"))
    )
    (net (code "118") (name "unconnected-(JP13-Pad1)") (class "Default")
      (node (ref "JP13") (pin "1") (pinfunction "1_1") (pintype "passive"))
    )
    (net (code "119") (name "unconnected-(JP13-Pad2)") (class "Default")
      (node (ref "JP13") (pin "2") (pinfunction "2_2") (pintype "passive"))
    )
    (net (code "120") (name "unconnected-(JP13-Pad3)") (class "Default")
      (node (ref "JP13") (pin "3") (pinfunction "3_3") (pintype "passive"))
    )
    (net (code "121") (name "unconnected-(JP13-Pad4)") (class "Default")
      (node (ref "JP13") (pin "4") (pinfunction "4_4") (pintype "passive"))
    )
    (net (code "122") (name "unconnected-(JP13-Pad5)") (class "Default")
      (node (ref "JP13") (pin "5") (pinfunction "5_5") (pintype "passive"))
    )
    (net (code "123") (name "unconnected-(JP13-Pad6)") (class "Default")
      (node (ref "JP13") (pin "6") (pinfunction "6_6") (pintype "passive"))
    )
    (net (code "124") (name "unconnected-(JP13-Pad7)") (class "Default")
      (node (ref "JP13") (pin "7") (pinfunction "7_7") (pintype "passive"))
    )
    (net (code "125") (name "unconnected-(JP13-Pad8)") (class "Default")
      (node (ref "JP13") (pin "8") (pinfunction "8_8") (pintype "passive"))
    )
    (net (code "126") (name "unconnected-(JP14-Pad1)") (class "Default")
      (node (ref "JP14") (pin "1") (pinfunction "1_1") (pintype "passive"))
    )
    (net (code "127") (name "unconnected-(JP14-Pad2)") (class "Default")
      (node (ref "JP14") (pin "2") (pinfunction "2_2") (pintype "passive"))
    )
    (net (code "128") (name "unconnected-(JP14-Pad3)") (class "Default")
      (node (ref "JP14") (pin "3") (pinfunction "3_3") (pintype "passive"))
    )
    (net (code "129") (name "unconnected-(JP14-Pad4)") (class "Default")
      (node (ref "JP14") (pin "4") (pinfunction "4_4") (pintype "passive"))
    )
    (net (code "130") (name "unconnected-(JP14-Pad5)") (class "Default")
      (node (ref "JP14") (pin "5") (pinfunction "5_5") (pintype "passive"))
    )
    (net (code "131") (name "unconnected-(JP14-Pad6)") (class "Default")
      (node (ref "JP14") (pin "6") (pinfunction "6_6") (pintype "passive"))
    )
    (net (code "132") (name "unconnected-(JP14-Pad7)") (class "Default")
      (node (ref "JP14") (pin "7") (pinfunction "7_7") (pintype "passive"))
    )
    (net (code "133") (name "unconnected-(JP14-Pad8)") (class "Default")
      (node (ref "JP14") (pin "8") (pinfunction "8_8") (pintype "passive"))
    )
    (net (code "134") (name "unconnected-(JP15-Pad1)") (class "Default")
      (node (ref "JP15") (pin "1") (pinfunction "1_1") (pintype "passive"))
    )
    (net (code "135") (name "unconnected-(JP15-Pad2)") (class "Default")
      (node (ref "JP15") (pin "2") (pinfunction "2_2") (pintype "passive"))
    )
    (net (code "136") (name "unconnected-(JP15-Pad3)") (class "Default")
      (node (ref "JP15") (pin "3") (pinfunction "3_3") (pintype "passive"))
    )
    (net (code "137") (name "unconnected-(JP15-Pad4)") (class "Default")
      (node (ref "JP15") (pin "4") (pinfunction "4_4") (pintype "passive"))
    )
    (net (code "138") (name "unconnected-(JP15-Pad5)") (class "Default")
      (node (ref "JP15") (pin "5") (pinfunction "5_5") (pintype "passive"))
    )
    (net (code "139") (name "unconnected-(JP15-Pad6)") (class "Default")
      (node (ref "JP15") (pin "6") (pinfunction "6_6") (pintype "passive"))
    )
    (net (code "140") (name "unconnected-(JP15-Pad7)") (class "Default")
      (node (ref "JP15") (pin "7") (pinfunction "7_7") (pintype "passive"))
    )
    (net (code "141") (name "unconnected-(JP15-Pad8)") (class "Default")
      (node (ref "JP15") (pin "8") (pinfunction "8_8") (pintype "passive"))
    )
    (net (code "142") (name "unconnected-(JP18-Pad1)") (class "Default")
      (node (ref "JP18") (pin "1") (pinfunction "1_1") (pintype "passive"))
    )
    (net (code "143") (name "unconnected-(JP18-Pad2)") (class "Default")
      (node (ref "JP18") (pin "2") (pinfunction "2_2") (pintype "passive"))
    )
    (net (code "144") (name "unconnected-(JP18-Pad3)") (class "Default")
      (node (ref "JP18") (pin "3") (pinfunction "3_3") (pintype "passive"))
    )
    (net (code "145") (name "unconnected-(JP18-Pad4)") (class "Default")
      (node (ref "JP18") (pin "4") (pinfunction "4_4") (pintype "passive"))
    )
    (net (code "146") (name "unconnected-(JP19-Pad1)") (class "Default")
      (node (ref "JP19") (pin "1") (pinfunction "1_1") (pintype "passive"))
    )
    (net (code "147") (name "unconnected-(JP19-Pad2)") (class "Default")
      (node (ref "JP19") (pin "2") (pinfunction "2_2") (pintype "passive"))
    )
    (net (code "148") (name "unconnected-(JP19-Pad3)") (class "Default")
      (node (ref "JP19") (pin "3") (pinfunction "3_3") (pintype "passive"))
    )
    (net (code "149") (name "unconnected-(JP19-Pad4)") (class "Default")
      (node (ref "JP19") (pin "4") (pinfunction "4_4") (pintype "passive"))
    )
    (net (code "150") (name "unconnected-(JP21-Pad1)") (class "Default")
      (node (ref "JP21") (pin "1") (pinfunction "1_1") (pintype "passive"))
    )
    (net (code "151") (name "unconnected-(JP21-Pad2)") (class "Default")
      (node (ref "JP21") (pin "2") (pinfunction "2_2") (pintype "passive"))
    )
    (net (code "152") (name "unconnected-(JP21-Pad3)") (class "Default")
      (node (ref "JP21") (pin "3") (pinfunction "3_3") (pintype "passive"))
    )
    (net (code "153") (name "unconnected-(JP21-Pad4)") (class "Default")
      (node (ref "JP21") (pin "4") (pinfunction "4_4") (pintype "passive"))
    )
    (net (code "154") (name "unconnected-(JP27-Pad1)") (class "Default")
      (node (ref "JP27") (pin "1") (pinfunction "1_1") (pintype "passive"))
    )
    (net (code "155") (name "unconnected-(JP27-Pad2)") (class "Default")
      (node (ref "JP27") (pin "2") (pinfunction "2_2") (pintype "passive"))
    )
    (net (code "156") (name "unconnected-(JP27-Pad3)") (class "Default")
      (node (ref "JP27") (pin "3") (pinfunction "3_3") (pintype "passive"))
    )
    (net (code "157") (name "unconnected-(JP27-Pad4)") (class "Default")
      (node (ref "JP27") (pin "4") (pinfunction "4_4") (pintype "passive"))
    )
    (net (code "158") (name "unconnected-(JP27-Pad5)") (class "Default")
      (node (ref "JP27") (pin "5") (pinfunction "5_5") (pintype "passive"))
    )
    (net (code "159") (name "unconnected-(JP28-Pad1)") (class "Default")
      (node (ref "JP28") (pin "1") (pinfunction "1_1") (pintype "passive"))
    )
    (net (code "160") (name "unconnected-(JP28-Pad2)") (class "Default")
      (node (ref "JP28") (pin "2") (pinfunction "2_2") (pintype "passive"))
    )
    (net (code "161") (name "unconnected-(JP28-Pad3)") (class "Default")
      (node (ref "JP28") (pin "3") (pinfunction "3_3") (pintype "passive"))
    )
    (net (code "162") (name "unconnected-(JP28-Pad4)") (class "Default")
      (node (ref "JP28") (pin "4") (pinfunction "4_4") (pintype "passive"))
    )
    (net (code "163") (name "unconnected-(JP28-Pad5)") (class "Default")
      (node (ref "JP28") (pin "5") (pinfunction "5_5") (pintype "passive"))
    )
    (net (code "164") (name "unconnected-(JP29-Pad1)") (class "Default")
      (node (ref "JP29") (pin "1") (pinfunction "1_1") (pintype "passive"))
    )
    (net (code "165") (name "unconnected-(JP29-Pad2)") (class "Default")
      (node (ref "JP29") (pin "2") (pinfunction "2_2") (pintype "passive"))
    )
    (net (code "166") (name "unconnected-(JP29-Pad3)") (class "Default")
      (node (ref "JP29") (pin "3") (pinfunction "3_3") (pintype "passive"))
    )
    (net (code "167") (name "unconnected-(JP29-Pad4)") (class "Default")
      (node (ref "JP29") (pin "4") (pinfunction "4_4") (pintype "passive"))
    )
    (net (code "168") (name "unconnected-(JP29-Pad5)") (class "Default")
      (node (ref "JP29") (pin "5") (pinfunction "5_5") (pintype "passive"))
    )
    (net (code "169") (name "unconnected-(JP30-Pad1)") (class "Default")
      (node (ref "JP30") (pin "1") (pinfunction "1_1") (pintype "passive"))
    )
    (net (code "170") (name "unconnected-(JP30-Pad2)") (class "Default")
      (node (ref "JP30") (pin "2") (pinfunction "2_2") (pintype "passive"))
    )
    (net (code "171") (name "unconnected-(JP30-Pad3)") (class "Default")
      (node (ref "JP30") (pin "3") (pinfunction "3_3") (pintype "passive"))
    )
    (net (code "172") (name "unconnected-(JP30-Pad4)") (class "Default")
      (node (ref "JP30") (pin "4") (pinfunction "4_4") (pintype "passive"))
    )
    (net (code "173") (name "unconnected-(JP30-Pad5)") (class "Default")
      (node (ref "JP30") (pin "5") (pinfunction "5_5") (pintype "passive"))
    )
    (net (code "174") (name "unconnected-(JP31-Pad1)") (class "Default")
      (node (ref "JP31") (pin "1") (pinfunction "1_1") (pintype "passive"))
    )
    (net (code "175") (name "unconnected-(JP31-Pad2)") (class "Default")
      (node (ref "JP31") (pin "2") (pinfunction "2_2") (pintype "passive"))
    )
    (net (code "176") (name "unconnected-(JP31-Pad3)") (class "Default")
      (node (ref "JP31") (pin "3") (pinfunction "3_3") (pintype "passive"))
    )
    (net (code "177") (name "unconnected-(JP31-Pad4)") (class "Default")
      (node (ref "JP31") (pin "4") (pinfunction "4_4") (pintype "passive"))
    )
    (net (code "178") (name "unconnected-(JP31-Pad5)") (class "Default")
      (node (ref "JP31") (pin "5") (pinfunction "5_5") (pintype "passive"))
    )
    (net (code "179") (name "unconnected-(U$1-Pad1)") (class "Default")
      (node (ref "U$1") (pin "1") (pinfunction "1_1") (pintype "passive"))
    )
    (net (code "180") (name "unconnected-(U$2-Pad1)") (class "Default")
      (node (ref "U$2") (pin "1") (pinfunction "1_1") (pintype "passive"))
    )
    (net (code "181") (name "unconnected-(U$3-Pad1)") (class "Default")
      (node (ref "U$3") (pin "1") (pinfunction "1_1") (pintype "passive"))
    )
    (net (code "182") (name "unconnected-(U$4-Pad4)") (class "Default")
      (node (ref "U$4") (pin "4") (pinfunction "4_4") (pintype "input"))
    )
  )
)
